# HealthMonitor.net
KiCad netlist of a schematic drawn in EAGLE
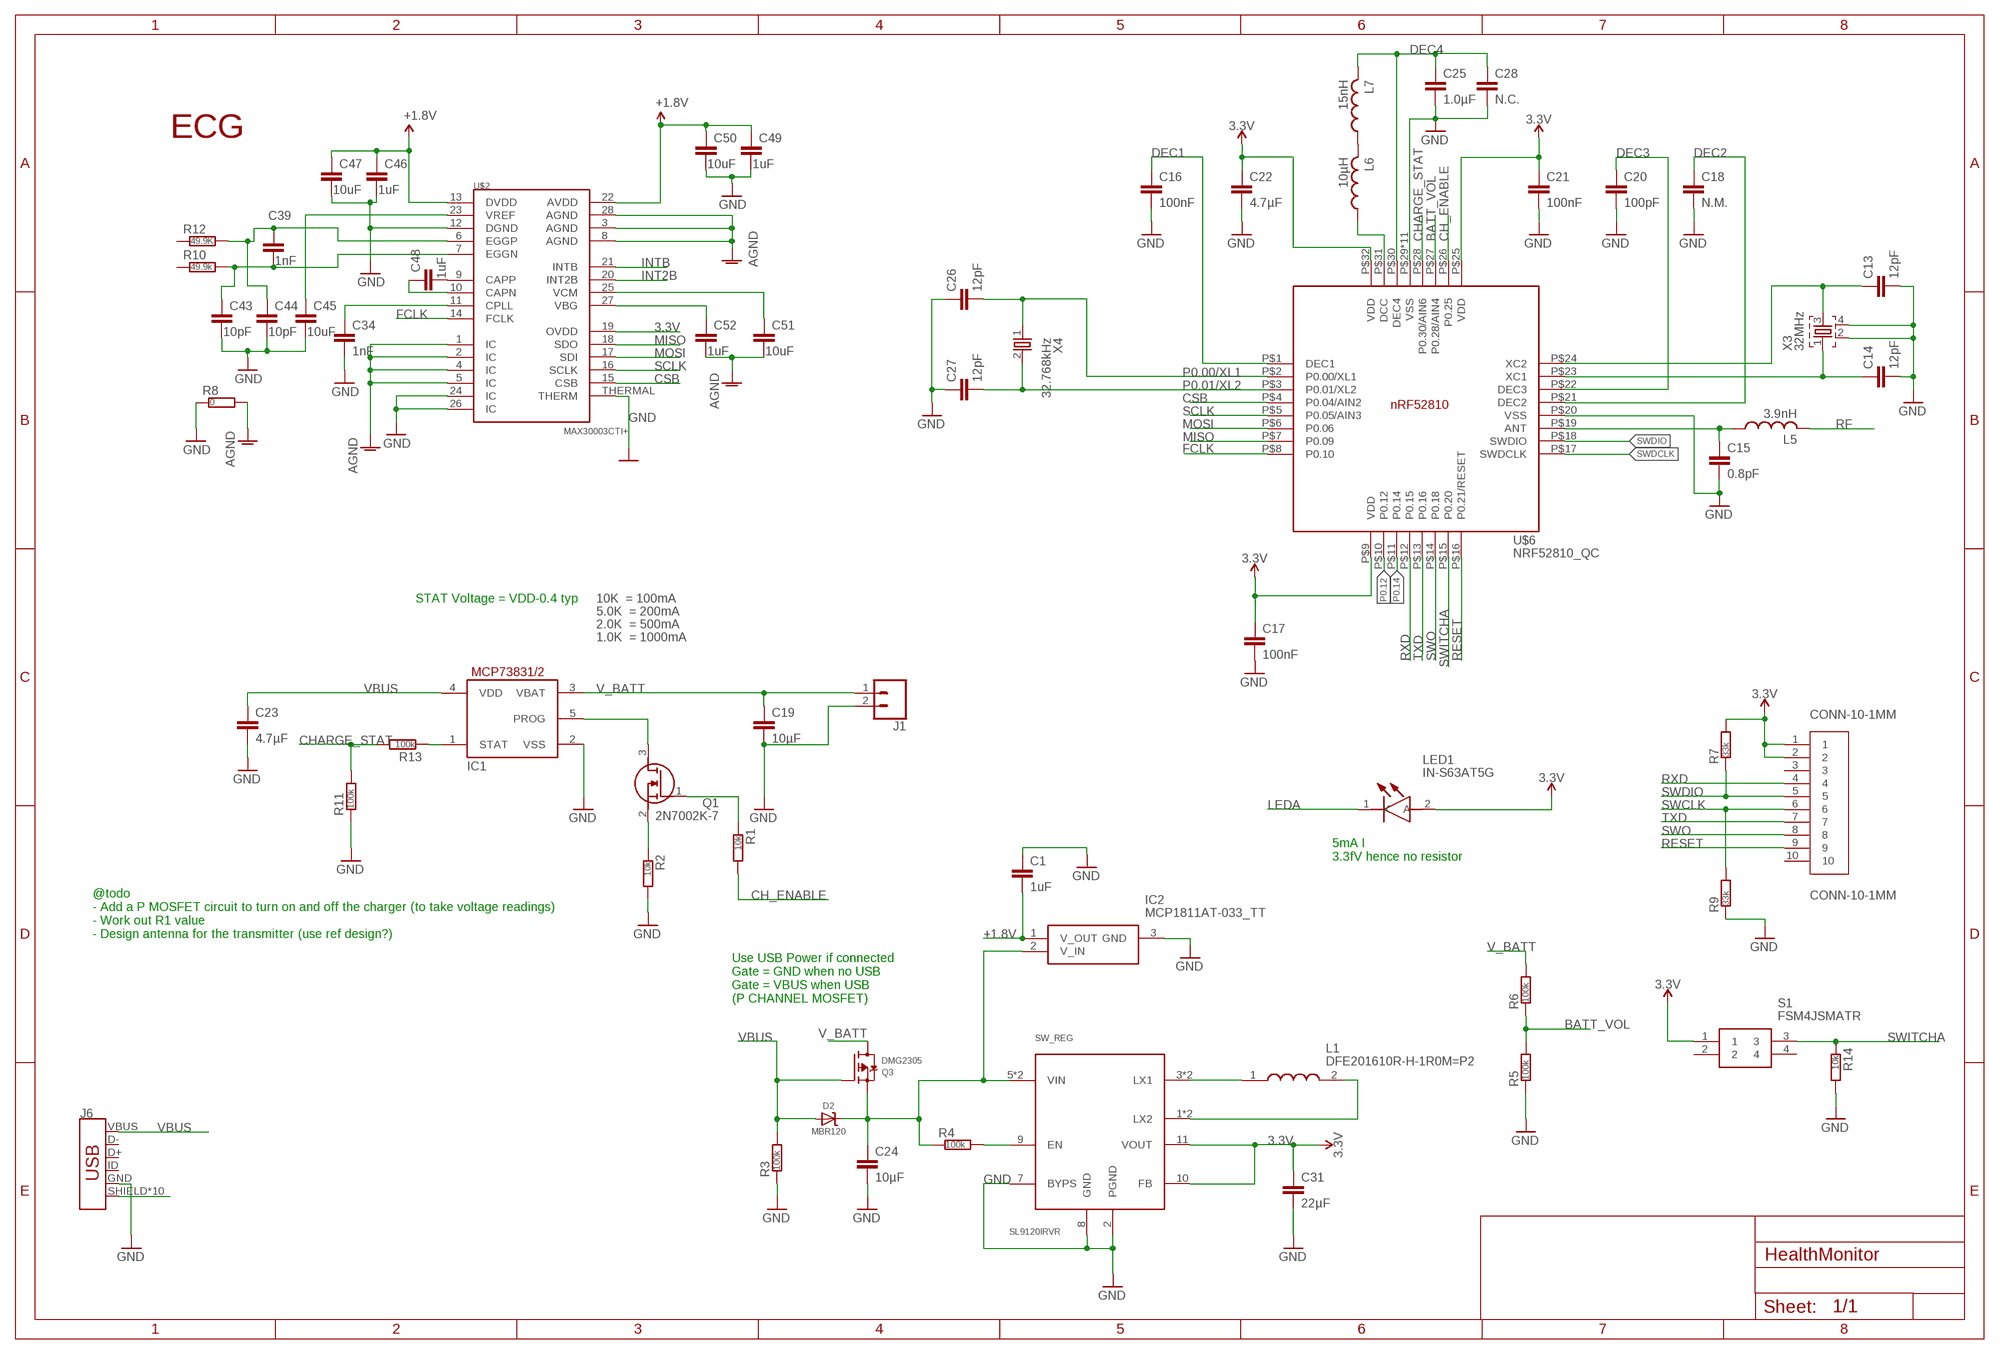
[diagram p0: schematic, sheet 1]

(export (version "E")
  (design (tool "Eeschema 10.0.6"))
  (components
    (comp (ref "C1")
      (value "1uF")
      (footprint "eagle-import:RESC0402_N")
      (libsource (lib "eagle-import") (part "CAPACITOR_0402_N"))
    )
    (comp (ref "C13")
      (value "12pF")
      (footprint "eagle-import:RESC0402_N")
      (libsource (lib "eagle-import") (part "CAPACITOR_0402_N"))
    )
    (comp (ref "C14")
      (value "12pF")
      (footprint "eagle-import:RESC0402_N")
      (libsource (lib "eagle-import") (part "CAPACITOR_0402_N"))
    )
    (comp (ref "C15")
      (value "0.8pF")
      (footprint "eagle-import:RESC0402_N")
      (libsource (lib "eagle-import") (part "CAPACITOR_0402_N"))
    )
    (comp (ref "C16")
      (value "100nF")
      (footprint "eagle-import:RESC0402_N")
      (libsource (lib "eagle-import") (part "CAPACITOR_0402_N"))
    )
    (comp (ref "C17")
      (value "100nF")
      (footprint "eagle-import:RESC0402_N")
      (libsource (lib "eagle-import") (part "CAPACITOR_0402_N"))
    )
    (comp (ref "C18")
      (value "N.M.")
      (footprint "eagle-import:RESC0402_N")
      (libsource (lib "eagle-import") (part "CAPACITOR_0402_N"))
    )
    (comp (ref "C19")
      (value "10µF")
      (footprint "eagle-import:RESC0603_N")
      (libsource (lib "eagle-import") (part "CAPACITOR_0603_N"))
    )
    (comp (ref "C20")
      (value "100pF")
      (footprint "eagle-import:RESC0402_N")
      (libsource (lib "eagle-import") (part "CAPACITOR_0402_N"))
    )
    (comp (ref "C21")
      (value "100nF")
      (footprint "eagle-import:RESC0402_N")
      (libsource (lib "eagle-import") (part "CAPACITOR_0402_N"))
    )
    (comp (ref "C22")
      (value "4.7µF")
      (footprint "eagle-import:RESC0603_N")
      (libsource (lib "eagle-import") (part "CAPACITOR_0603_N"))
    )
    (comp (ref "C23")
      (value "4.7µF")
      (footprint "eagle-import:RESC0603_N")
      (libsource (lib "eagle-import") (part "CAPACITOR_0603_N"))
    )
    (comp (ref "C24")
      (value "10µF")
      (footprint "eagle-import:RESC0603_N")
      (libsource (lib "eagle-import") (part "CAPACITOR_0603_N"))
    )
    (comp (ref "C25")
      (value "1.0µF")
      (footprint "eagle-import:RESC0603_N")
      (libsource (lib "eagle-import") (part "CAPACITOR_0603_N"))
    )
    (comp (ref "C26")
      (value "12pF")
      (footprint "eagle-import:RESC0402_N")
      (libsource (lib "eagle-import") (part "CAPACITOR_0402_N"))
    )
    (comp (ref "C27")
      (value "12pF")
      (footprint "eagle-import:RESC0402_N")
      (libsource (lib "eagle-import") (part "CAPACITOR_0402_N"))
    )
    (comp (ref "C28")
      (value "N.C.")
      (footprint "eagle-import:RESC0402_N")
      (libsource (lib "eagle-import") (part "CAPACITOR_0402_N"))
    )
    (comp (ref "C31")
      (value "22µF")
      (footprint "eagle-import:RESC0603_N")
      (libsource (lib "eagle-import") (part "CAPACITOR_0603_N"))
    )
    (comp (ref "C34")
      (value "1nF")
      (footprint "eagle-import:C0805")
      (libsource (lib "eagle-import") (part "C-EUC0805"))
    )
    (comp (ref "C39")
      (value "1nF")
      (footprint "eagle-import:RESC0603_N")
      (libsource (lib "eagle-import") (part "CAPACITOR_0603_N"))
    )
    (comp (ref "C43")
      (value "10pF")
      (footprint "eagle-import:RESC0603_N")
      (libsource (lib "eagle-import") (part "CAPACITOR_0603_N"))
    )
    (comp (ref "C44")
      (value "10pF")
      (footprint "eagle-import:RESC0603_N")
      (libsource (lib "eagle-import") (part "CAPACITOR_0603_N"))
    )
    (comp (ref "C45")
      (value "10uF")
      (footprint "eagle-import:RESC0603_N")
      (libsource (lib "eagle-import") (part "CAPACITOR_0603_N"))
    )
    (comp (ref "C46")
      (value "1uF")
      (footprint "eagle-import:RESC0603_N")
      (libsource (lib "eagle-import") (part "CAPACITOR_0603_N"))
    )
    (comp (ref "C47")
      (value "10uF")
      (footprint "eagle-import:RESC0603_N")
      (libsource (lib "eagle-import") (part "CAPACITOR_0603_N"))
    )
    (comp (ref "C48")
      (value "1uF")
      (footprint "eagle-import:RESC0603_N")
      (libsource (lib "eagle-import") (part "CAPACITOR_0603_N"))
    )
    (comp (ref "C49")
      (value "1uF")
      (footprint "eagle-import:RESC0603_N")
      (libsource (lib "eagle-import") (part "CAPACITOR_0603_N"))
    )
    (comp (ref "C50")
      (value "10uF")
      (footprint "eagle-import:RESC0603_N")
      (libsource (lib "eagle-import") (part "CAPACITOR_0603_N"))
    )
    (comp (ref "C51")
      (value "10uF")
      (footprint "eagle-import:RESC0603_N")
      (libsource (lib "eagle-import") (part "CAPACITOR_0603_N"))
    )
    (comp (ref "C52")
      (value "1uF")
      (footprint "eagle-import:RESC0603_N")
      (libsource (lib "eagle-import") (part "CAPACITOR_0603_N"))
    )
    (comp (ref "D2")
      (value "MBR120")
      (footprint "eagle-import:SOD-123")
      (libsource (lib "eagle-import") (part "DIODE-SCHOTTKYSOD-123"))
    )
    (comp (ref "IC1")
      (value "MCP73831/OT")
      (footprint "eagle-import:SOT23-5L")
      (libsource (lib "eagle-import") (part "MCP73831/OT"))
    )
    (comp (ref "IC2")
      (value "MCP1811AT-033_TT")
      (footprint "eagle-import:SOT95P237X112-3N")
      (fields
        (field (name "MANUFACTURER_PART_NUMBER") "MCP1811AT-033/TT")
        (field (name "MOUSER_PART_NUMBER") "579-MCP1811AT-033/TT")
      )
      (libsource (lib "eagle-import") (part "MCP1811AT-033_TT"))
    )
    (comp (ref "J1")
      (value "CONN_02")
      (footprint "eagle-import:1X02")
      (libsource (lib "eagle-import") (part "CONN_02"))
    )
    (comp (ref "J6")
      (value "USB_MICRO-B_HALF_PTH_MILL")
      (footprint "eagle-import:USB-MICROB-PTH-MILL")
      (libsource (lib "eagle-import") (part "USB_MICRO-B_HALF_PTH_MILL"))
    )
    (comp (ref "L1")
      (value "DFE201610R-H-1R0M=P2")
      (footprint "eagle-import:INDC2016X100N")
      (fields (field (name "MOUSER_PART_NUMBER") "81-DFE201610RH1R0MP2"))
      (libsource (lib "eagle-import") (part "DFE201610R-H-1R0M=P2"))
    )
    (comp (ref "L5")
      (value "3.9nH")
      (footprint "eagle-import:RESC0402_N")
      (libsource (lib "eagle-import") (part "INDUCTOR_0402_N"))
    )
    (comp (ref "L6")
      (value "10µH")
      (footprint "eagle-import:RESC0603_N")
      (libsource (lib "eagle-import") (part "INDUCTOR_0603_N"))
    )
    (comp (ref "L7")
      (value "15nH")
      (footprint "eagle-import:RESC0402_N")
      (libsource (lib "eagle-import") (part "INDUCTOR_0402_N"))
    )
    (comp (ref "LED1")
      (value "IN-S63AT5G")
      (footprint "eagle-import:LEDM168X39N")
      (fields (field (name "MOUSER_PART_NUMBER") "743-IN-S63AT5G"))
      (libsource (lib "eagle-import") (part "IN-S63AT5G"))
    )
    (comp (ref "Q1")
      (value "2N7002K-7")
      (footprint "eagle-import:SOT96P240X100-3N")
      (fields (field (name "MOUSER_PART_NUMBER") "621-2N7002K-7") (field (name "RS_PART_NUMBER") "7703383"))
      (libsource (lib "eagle-import") (part "2N7002K-7"))
    )
    (comp (ref "Q3")
      (value "DMG2305")
      (footprint "eagle-import:SOT23-R")
      (libsource (lib "eagle-import") (part "MOSFET-P"))
    )
    (comp (ref "R1")
      (value "10k")
      (footprint "eagle-import:RESC0402_N")
      (libsource (lib "eagle-import") (part "RESISTOR_0402_N"))
    )
    (comp (ref "R2")
      (value "10k")
      (footprint "eagle-import:RESC0402_N")
      (libsource (lib "eagle-import") (part "RESISTOR_0402_N"))
    )
    (comp (ref "R3")
      (value "100k")
      (footprint "eagle-import:RESC0402_N")
      (libsource (lib "eagle-import") (part "RESISTOR_0402_N"))
    )
    (comp (ref "R4")
      (value "100k")
      (footprint "eagle-import:RESC0402_N")
      (libsource (lib "eagle-import") (part "RESISTOR_0402_N"))
    )
    (comp (ref "R5")
      (value "100k")
      (footprint "eagle-import:RESC0402_N")
      (libsource (lib "eagle-import") (part "RESISTOR_0402_N"))
    )
    (comp (ref "R6")
      (value "100k")
      (footprint "eagle-import:RESC0402_N")
      (libsource (lib "eagle-import") (part "RESISTOR_0402_N"))
    )
    (comp (ref "R7")
      (value "33k")
      (footprint "eagle-import:RESC0402_N")
      (libsource (lib "eagle-import") (part "RESISTOR_0402_N"))
    )
    (comp (ref "R8")
      (value "0")
      (footprint "eagle-import:RESC0402_N")
      (libsource (lib "eagle-import") (part "RESISTOR_0402_N"))
    )
    (comp (ref "R9")
      (value "33k")
      (footprint "eagle-import:RESC0402_N")
      (libsource (lib "eagle-import") (part "RESISTOR_0402_N"))
    )
    (comp (ref "R10")
      (value "49.9k")
      (footprint "eagle-import:RESC0402_N")
      (libsource (lib "eagle-import") (part "RESISTOR_0402_N"))
    )
    (comp (ref "R11")
      (value "100k")
      (footprint "eagle-import:RESC0402_N")
      (libsource (lib "eagle-import") (part "RESISTOR_0402_N"))
    )
    (comp (ref "R12")
      (value "49.9K")
      (footprint "eagle-import:RESC0402_N")
      (libsource (lib "eagle-import") (part "RESISTOR_0402_N"))
    )
    (comp (ref "R13")
      (value "100k")
      (footprint "eagle-import:RESC0402_N")
      (libsource (lib "eagle-import") (part "RESISTOR_0402_N"))
    )
    (comp (ref "R14")
      (value "10k")
      (footprint "eagle-import:RESC0402_N")
      (libsource (lib "eagle-import") (part "RESISTOR_0402_N"))
    )
    (comp (ref "S1")
      (value "FSM4JSMATR")
      (footprint "eagle-import:FSM4JSMATR")
      (fields (field (name "MOUSER_PART_NUMBER") "506-FSM4JSMATR") (field (name "RS_PART_NUMBER") "7182455P"))
      (libsource (lib "eagle-import") (part "FSM4JSMATR"))
    )
    (comp (ref "SW_REG")
      (value "SL9120IRVR")
      (footprint "eagle-import:TQFN-12")
      (libsource (lib "eagle-import") (part "SL9120IRVR"))
    )
    (comp (ref "U$1")
      (value "CONN-10-1MM")
      (footprint "eagle-import:CONN-10-1MM")
      (libsource (lib "eagle-import") (part "CONN-10-1MM"))
    )
    (comp (ref "U$2")
      (value "MAX30003CTI+")
      (footprint "eagle-import:QFN-28")
      (libsource (lib "eagle-import") (part "MAX30003"))
    )
    (comp (ref "U$6")
      (value "NRF52810_QC")
      (footprint "eagle-import:QFN50P500X500X90-32_N")
      (libsource (lib "eagle-import") (part "NRF52810_QC"))
    )
    (comp (ref "X3")
      (value "32MHz")
      (footprint "eagle-import:BT-XTAL_2016_N")
      (libsource (lib "eagle-import") (part "XTAL_32MHZ"))
    )
    (comp (ref "X4")
      (value "32.768kHz")
      (footprint "eagle-import:XTAL_3215_N")
      (libsource (lib "eagle-import") (part "XTAL_32KHZ"))
    )
  )
  (nets
    (net (code "1") (name "+1.8V") (class "Default")
      (node (ref "C1") (pin "2") (pinfunction "2_2") (pintype "passive"))
      (node (ref "C46") (pin "1") (pinfunction "1_1") (pintype "passive"))
      (node (ref "C47") (pin "1") (pinfunction "1_1") (pintype "passive"))
      (node (ref "C49") (pin "1") (pinfunction "1_1") (pintype "passive"))
      (node (ref "C50") (pin "1") (pinfunction "1_1") (pintype "passive"))
      (node (ref "IC2") (pin "1") (pinfunction "V_OUT_1") (pintype "bidirectional"))
      (node (ref "U$2") (pin "13") (pinfunction "DVDD_13") (pintype "bidirectional"))
      (node (ref "U$2") (pin "22") (pinfunction "AVDD_22") (pintype "bidirectional"))
    )
    (net (code "2") (name "/BATT_VOL") (class "Default")
      (node (ref "R5") (pin "2") (pinfunction "2_2") (pintype "passive"))
      (node (ref "R6") (pin "1") (pinfunction "1_1") (pintype "passive"))
      (node (ref "U$6") (pin "P$27") (pinfunction "P0.28/AIN4_P$27") (pintype "bidirectional"))
    )
    (net (code "3") (name "/CHARGE_STAT") (class "Default")
      (node (ref "R11") (pin "2") (pinfunction "2_2") (pintype "passive"))
      (node (ref "R13") (pin "2") (pinfunction "2_2") (pintype "passive"))
      (node (ref "U$6") (pin "P$28") (pinfunction "P0.30/AIN6_P$28") (pintype "bidirectional"))
    )
    (net (code "4") (name "/CH_ENABLE") (class "Default")
      (node (ref "R1") (pin "2") (pinfunction "2_2") (pintype "passive"))
      (node (ref "U$6") (pin "P$26") (pinfunction "P0.25_P$26") (pintype "bidirectional"))
    )
    (net (code "5") (name "/CSB") (class "Default")
      (node (ref "U$2") (pin "15") (pinfunction "CSB_15") (pintype "bidirectional"))
      (node (ref "U$6") (pin "P$4") (pinfunction "P0.04/AIN2_P$4") (pintype "bidirectional"))
    )
    (net (code "6") (name "/DEC1") (class "Default")
      (node (ref "C16") (pin "1") (pinfunction "1_1") (pintype "passive"))
      (node (ref "U$6") (pin "P$1") (pinfunction "DEC1_P$1") (pintype "bidirectional"))
    )
    (net (code "7") (name "/DEC2") (class "Default")
      (node (ref "C18") (pin "1") (pinfunction "1_1") (pintype "passive"))
      (node (ref "U$6") (pin "P$21") (pinfunction "DEC2_P$21") (pintype "bidirectional"))
    )
    (net (code "8") (name "/DEC3") (class "Default")
      (node (ref "C20") (pin "1") (pinfunction "1_1") (pintype "passive"))
      (node (ref "U$6") (pin "P$22") (pinfunction "DEC3_P$22") (pintype "bidirectional"))
    )
    (net (code "9") (name "/DEC4") (class "Default")
      (node (ref "C25") (pin "1") (pinfunction "1_1") (pintype "passive"))
      (node (ref "C28") (pin "1") (pinfunction "1_1") (pintype "passive"))
      (node (ref "L7") (pin "2") (pinfunction "2_2") (pintype "passive"))
      (node (ref "U$6") (pin "P$30") (pinfunction "DEC4_P$30") (pintype "bidirectional"))
    )
    (net (code "10") (name "/FCLK") (class "Default")
      (node (ref "U$2") (pin "14") (pinfunction "FCLK_14") (pintype "bidirectional"))
      (node (ref "U$6") (pin "P$8") (pinfunction "P0.10_P$8") (pintype "bidirectional"))
    )
    (net (code "11") (name "/INT2B") (class "Default")
      (node (ref "U$2") (pin "20") (pinfunction "INT2B_20") (pintype "bidirectional"))
    )
    (net (code "12") (name "/INTB") (class "Default")
      (node (ref "U$2") (pin "21") (pinfunction "INTB_21") (pintype "bidirectional"))
    )
    (net (code "13") (name "/LEDA") (class "Default")
      (node (ref "LED1") (pin "1") (pinfunction "K_1") (pintype "bidirectional"))
    )
    (net (code "14") (name "/MISO") (class "Default")
      (node (ref "U$2") (pin "18") (pinfunction "SDO_18") (pintype "bidirectional"))
      (node (ref "U$6") (pin "P$7") (pinfunction "P0.09_P$7") (pintype "bidirectional"))
    )
    (net (code "15") (name "/MOSI") (class "Default")
      (node (ref "U$2") (pin "17") (pinfunction "SDI_17") (pintype "bidirectional"))
      (node (ref "U$6") (pin "P$6") (pinfunction "P0.06_P$6") (pintype "bidirectional"))
    )
    (net (code "16") (name "/P0.00{slash}XL1") (class "Default")
      (node (ref "C26") (pin "2") (pinfunction "2_2") (pintype "passive"))
      (node (ref "U$6") (pin "P$2") (pinfunction "P0.00/XL1_P$2") (pintype "bidirectional"))
      (node (ref "X4") (pin "1") (pinfunction "1_1") (pintype "passive"))
    )
    (net (code "17") (name "/P0.01{slash}XL2") (class "Default")
      (node (ref "C27") (pin "2") (pinfunction "2_2") (pintype "passive"))
      (node (ref "U$6") (pin "P$3") (pinfunction "P0.01/XL2_P$3") (pintype "bidirectional"))
      (node (ref "X4") (pin "2") (pinfunction "2_2") (pintype "passive"))
    )
    (net (code "18") (name "/RESET") (class "Default")
      (node (ref "U$1") (pin "9") (pinfunction "9_9") (pintype "bidirectional"))
      (node (ref "U$6") (pin "P$16") (pinfunction "P0.21/RESET_P$16") (pintype "bidirectional"))
    )
    (net (code "19") (name "/RF") (class "Default")
      (node (ref "L5") (pin "2") (pinfunction "2_2") (pintype "passive"))
    )
    (net (code "20") (name "/RXD") (class "Default")
      (node (ref "U$1") (pin "4") (pinfunction "4_4") (pintype "bidirectional"))
      (node (ref "U$6") (pin "P$12") (pinfunction "P0.15_P$12") (pintype "bidirectional"))
    )
    (net (code "21") (name "/SCLK") (class "Default")
      (node (ref "U$2") (pin "16") (pinfunction "SCLK_16") (pintype "bidirectional"))
      (node (ref "U$6") (pin "P$5") (pinfunction "P0.05/AIN3_P$5") (pintype "bidirectional"))
    )
    (net (code "22") (name "/SWCLK") (class "Default")
      (node (ref "R9") (pin "2") (pinfunction "2_2") (pintype "passive"))
      (node (ref "U$1") (pin "6") (pinfunction "6_6") (pintype "bidirectional"))
    )
    (net (code "23") (name "/SWITCHA") (class "Default")
      (node (ref "R14") (pin "1") (pinfunction "1_1") (pintype "passive"))
      (node (ref "S1") (pin "3") (pinfunction "3_3") (pintype "bidirectional"))
      (node (ref "U$6") (pin "P$15") (pinfunction "P0.20_P$15") (pintype "bidirectional"))
    )
    (net (code "24") (name "/SWO") (class "Default")
      (node (ref "U$1") (pin "8") (pinfunction "8_8") (pintype "bidirectional"))
      (node (ref "U$6") (pin "P$14") (pinfunction "P0.18_P$14") (pintype "bidirectional"))
    )
    (net (code "25") (name "/TXD") (class "Default")
      (node (ref "U$1") (pin "7") (pinfunction "7_7") (pintype "bidirectional"))
      (node (ref "U$6") (pin "P$13") (pinfunction "P0.16_P$13") (pintype "bidirectional"))
    )
    (net (code "26") (name "/VBUS") (class "Default")
      (node (ref "C23") (pin "1") (pinfunction "1_1") (pintype "passive"))
      (node (ref "D2") (pin "A") (pinfunction "A_A") (pintype "passive"))
      (node (ref "IC1") (pin "4") (pinfunction "VDD_4") (pintype "power_in"))
      (node (ref "J6") (pin "VBUS") (pinfunction "VBUS_VBUS") (pintype "power_in"))
      (node (ref "Q3") (pin "1") (pinfunction "G_1") (pintype "passive"))
      (node (ref "R3") (pin "2") (pinfunction "2_2") (pintype "passive"))
    )
    (net (code "27") (name "/V_BATT") (class "Default")
      (node (ref "C19") (pin "1") (pinfunction "1_1") (pintype "passive"))
      (node (ref "IC1") (pin "3") (pinfunction "VBAT_3") (pintype "bidirectional"))
      (node (ref "J1") (pin "1") (pinfunction "1_1") (pintype "passive"))
      (node (ref "Q3") (pin "3") (pinfunction "D_3") (pintype "passive"))
      (node (ref "R6") (pin "2") (pinfunction "2_2") (pintype "passive"))
    )
    (net (code "28") (name "3.3V") (class "Default")
      (node (ref "C17") (pin "1") (pinfunction "1_1") (pintype "passive"))
      (node (ref "C21") (pin "1") (pinfunction "1_1") (pintype "passive"))
      (node (ref "C22") (pin "1") (pinfunction "1_1") (pintype "passive"))
      (node (ref "C31") (pin "1") (pinfunction "1_1") (pintype "passive"))
      (node (ref "LED1") (pin "2") (pinfunction "A_2") (pintype "bidirectional"))
      (node (ref "R7") (pin "2") (pinfunction "2_2") (pintype "passive"))
      (node (ref "S1") (pin "1") (pinfunction "1_1") (pintype "bidirectional"))
      (node (ref "SW_REG") (pin "10") (pinfunction "FB_10") (pintype "bidirectional"))
      (node (ref "SW_REG") (pin "11") (pinfunction "VOUT_11") (pintype "bidirectional"))
      (node (ref "U$1") (pin "1") (pinfunction "1_1") (pintype "bidirectional"))
      (node (ref "U$1") (pin "2") (pinfunction "2_2") (pintype "bidirectional"))
      (node (ref "U$2") (pin "19") (pinfunction "OVDD_19") (pintype "bidirectional"))
      (node (ref "U$6") (pin "P$25") (pinfunction "VDD_P$25") (pintype "bidirectional"))
      (node (ref "U$6") (pin "P$32") (pinfunction "VDD_P$32") (pintype "bidirectional"))
      (node (ref "U$6") (pin "P$9") (pinfunction "VDD_P$9") (pintype "bidirectional"))
    )
    (net (code "29") (name "AGND") (class "Default")
      (node (ref "C51") (pin "2") (pinfunction "2_2") (pintype "passive"))
      (node (ref "C52") (pin "2") (pinfunction "2_2") (pintype "passive"))
      (node (ref "R8") (pin "2") (pinfunction "2_2") (pintype "passive"))
      (node (ref "U$2") (pin "1") (pinfunction "IC_1") (pintype "bidirectional"))
      (node (ref "U$2") (pin "2") (pinfunction "IC_2") (pintype "bidirectional"))
      (node (ref "U$2") (pin "28") (pinfunction "AGND_28") (pintype "bidirectional"))
      (node (ref "U$2") (pin "3") (pinfunction "AGND_3") (pintype "bidirectional"))
      (node (ref "U$2") (pin "4") (pinfunction "IC_4") (pintype "bidirectional"))
      (node (ref "U$2") (pin "5") (pinfunction "IC_5") (pintype "bidirectional"))
      (node (ref "U$2") (pin "8") (pinfunction "AGND_8") (pintype "bidirectional"))
    )
    (net (code "30") (name "GND") (class "Default")
      (node (ref "C1") (pin "1") (pinfunction "1_1") (pintype "passive"))
      (node (ref "C13") (pin "2") (pinfunction "2_2") (pintype "passive"))
      (node (ref "C14") (pin "2") (pinfunction "2_2") (pintype "passive"))
      (node (ref "C15") (pin "2") (pinfunction "2_2") (pintype "passive"))
      (node (ref "C16") (pin "2") (pinfunction "2_2") (pintype "passive"))
      (node (ref "C17") (pin "2") (pinfunction "2_2") (pintype "passive"))
      (node (ref "C18") (pin "2") (pinfunction "2_2") (pintype "passive"))
      (node (ref "C19") (pin "2") (pinfunction "2_2") (pintype "passive"))
      (node (ref "C20") (pin "2") (pinfunction "2_2") (pintype "passive"))
      (node (ref "C21") (pin "2") (pinfunction "2_2") (pintype "passive"))
      (node (ref "C22") (pin "2") (pinfunction "2_2") (pintype "passive"))
      (node (ref "C23") (pin "2") (pinfunction "2_2") (pintype "passive"))
      (node (ref "C24") (pin "2") (pinfunction "2_2") (pintype "passive"))
      (node (ref "C25") (pin "2") (pinfunction "2_2") (pintype "passive"))
      (node (ref "C26") (pin "1") (pinfunction "1_1") (pintype "passive"))
      (node (ref "C27") (pin "1") (pinfunction "1_1") (pintype "passive"))
      (node (ref "C28") (pin "2") (pinfunction "2_2") (pintype "passive"))
      (node (ref "C31") (pin "2") (pinfunction "2_2") (pintype "passive"))
      (node (ref "C34") (pin "2") (pinfunction "2_2") (pintype "passive"))
      (node (ref "C43") (pin "2") (pinfunction "2_2") (pintype "passive"))
      (node (ref "C44") (pin "2") (pinfunction "2_2") (pintype "passive"))
      (node (ref "C45") (pin "2") (pinfunction "2_2") (pintype "passive"))
      (node (ref "C46") (pin "2") (pinfunction "2_2") (pintype "passive"))
      (node (ref "C47") (pin "2") (pinfunction "2_2") (pintype "passive"))
      (node (ref "C49") (pin "2") (pinfunction "2_2") (pintype "passive"))
      (node (ref "C50") (pin "2") (pinfunction "2_2") (pintype "passive"))
      (node (ref "IC1") (pin "2") (pinfunction "VSS_2") (pintype "power_in"))
      (node (ref "IC2") (pin "3") (pinfunction "GND_3") (pintype "bidirectional"))
      (node (ref "J1") (pin "2") (pinfunction "2_2") (pintype "passive"))
      (node (ref "J6") (pin "GND") (pinfunction "GND_GND") (pintype "power_in"))
      (node (ref "R11") (pin "1") (pinfunction "1_1") (pintype "passive"))
      (node (ref "R14") (pin "2") (pinfunction "2_2") (pintype "passive"))
      (node (ref "R2") (pin "2") (pinfunction "2_2") (pintype "passive"))
      (node (ref "R3") (pin "1") (pinfunction "1_1") (pintype "passive"))
      (node (ref "R5") (pin "1") (pinfunction "1_1") (pintype "passive"))
      (node (ref "R8") (pin "1") (pinfunction "1_1") (pintype "passive"))
      (node (ref "R9") (pin "1") (pinfunction "1_1") (pintype "passive"))
      (node (ref "SW_REG") (pin "2") (pinfunction "PGND_2") (pintype "bidirectional"))
      (node (ref "SW_REG") (pin "7") (pinfunction "BYPS_7") (pintype "bidirectional"))
      (node (ref "SW_REG") (pin "8") (pinfunction "GND_8") (pintype "bidirectional"))
      (node (ref "U$2") (pin "12") (pinfunction "DGND_12") (pintype "bidirectional"))
      (node (ref "U$2") (pin "24") (pinfunction "IC_24") (pintype "bidirectional"))
      (node (ref "U$2") (pin "26") (pinfunction "IC_26") (pintype "bidirectional"))
      (node (ref "U$2") (pin "THERMAL") (pinfunction "THERM_THERMAL") (pintype "bidirectional"))
      (node (ref "U$6") (pin "P$20") (pinfunction "VSS_P$20") (pintype "bidirectional"))
      (node (ref "U$6") (pin "P$29") (pinfunction "VSS_P$29") (pintype "bidirectional"))
      (node (ref "U$6") (pin "P$33") (pinfunction "VSS_P$33") (pintype "bidirectional"))
      (node (ref "U$6") (pin "P$34") (pinfunction "VSS_P$34") (pintype "bidirectional"))
      (node (ref "U$6") (pin "P$35") (pinfunction "VSS_P$35") (pintype "bidirectional"))
      (node (ref "U$6") (pin "P$36") (pinfunction "VSS_P$36") (pintype "bidirectional"))
      (node (ref "U$6") (pin "P$37") (pinfunction "VSS_P$37") (pintype "bidirectional"))
      (node (ref "U$6") (pin "P$38") (pinfunction "VSS_P$38") (pintype "bidirectional"))
      (node (ref "U$6") (pin "P$39") (pinfunction "VSS_P$39") (pintype "bidirectional"))
      (node (ref "U$6") (pin "P$40") (pinfunction "VSS_P$40") (pintype "bidirectional"))
      (node (ref "U$6") (pin "P$41") (pinfunction "VSS_P$41") (pintype "bidirectional"))
      (node (ref "U$6") (pin "P$42") (pinfunction "VSS_P$42") (pintype "bidirectional"))
      (node (ref "X3") (pin "2") (pinfunction "2_2") (pintype "passive"))
      (node (ref "X3") (pin "4") (pinfunction "4_4") (pintype "passive"))
    )
    (net (code "31") (name "Net-(IC1-PROG)") (class "Default")
      (node (ref "IC1") (pin "5") (pinfunction "PROG_5") (pintype "input"))
      (node (ref "Q1") (pin "3") (pinfunction "D_3") (pintype "bidirectional"))
    )
    (net (code "32") (name "Net-(IC1-STAT)") (class "Default")
      (node (ref "IC1") (pin "1") (pinfunction "STAT_1") (pintype "output"))
      (node (ref "R13") (pin "1") (pinfunction "1_1") (pintype "passive"))
    )
    (net (code "33") (name "Net-(IC2-V_IN)") (class "Default")
      (node (ref "C24") (pin "1") (pinfunction "1_1") (pintype "passive"))
      (node (ref "D2") (pin "C") (pinfunction "C_C") (pintype "passive"))
      (node (ref "IC2") (pin "2") (pinfunction "V_IN_2") (pintype "bidirectional"))
      (node (ref "Q3") (pin "2") (pinfunction "S_2") (pintype "passive"))
      (node (ref "R4") (pin "1") (pinfunction "1_1") (pintype "passive"))
      (node (ref "SW_REG") (pin "5") (pinfunction "VIN_5") (pintype "bidirectional"))
      (node (ref "SW_REG") (pin "6") (pinfunction "VIN_6") (pintype "bidirectional"))
    )
    (net (code "34") (name "Net-(J6-PadSHIELD)") (class "Default")
      (node (ref "J6") (pin "SHIELD") (pinfunction "SHIELD_SHIELD") (pintype "bidirectional"))
      (node (ref "J6") (pin "SHIELD10") (pinfunction "SHIELD_SHIELD10") (pintype "bidirectional"))
      (node (ref "J6") (pin "SHIELD2") (pinfunction "SHIELD_SHIELD2") (pintype "bidirectional"))
      (node (ref "J6") (pin "SHIELD3") (pinfunction "SHIELD_SHIELD3") (pintype "bidirectional"))
      (node (ref "J6") (pin "SHIELD4") (pinfunction "SHIELD_SHIELD4") (pintype "bidirectional"))
      (node (ref "J6") (pin "SHIELD5") (pinfunction "SHIELD_SHIELD5") (pintype "bidirectional"))
      (node (ref "J6") (pin "SHIELD6") (pinfunction "SHIELD_SHIELD6") (pintype "bidirectional"))
      (node (ref "J6") (pin "SHIELD7") (pinfunction "SHIELD_SHIELD7") (pintype "bidirectional"))
      (node (ref "J6") (pin "SHIELD8") (pinfunction "SHIELD_SHIELD8") (pintype "bidirectional"))
      (node (ref "J6") (pin "SHIELD9") (pinfunction "SHIELD_SHIELD9") (pintype "bidirectional"))
    )
    (net (code "35") (name "Net-(L1-Pad1)") (class "Default")
      (node (ref "L1") (pin "1") (pinfunction "1_1") (pintype "bidirectional"))
      (node (ref "SW_REG") (pin "3") (pinfunction "LX1_3") (pintype "bidirectional"))
      (node (ref "SW_REG") (pin "4") (pinfunction "LX1_4") (pintype "bidirectional"))
    )
    (net (code "36") (name "Net-(L1-Pad2)") (class "Default")
      (node (ref "L1") (pin "2") (pinfunction "2_2") (pintype "bidirectional"))
      (node (ref "SW_REG") (pin "1") (pinfunction "LX2_1") (pintype "bidirectional"))
      (node (ref "SW_REG") (pin "12") (pinfunction "LX2_12") (pintype "bidirectional"))
    )
    (net (code "37") (name "Net-(L6-Pad2)") (class "Default")
      (node (ref "L6") (pin "2") (pinfunction "2_2") (pintype "passive"))
      (node (ref "L7") (pin "1") (pinfunction "1_1") (pintype "passive"))
    )
    (net (code "38") (name "Net-(Q1-G)") (class "Default")
      (node (ref "Q1") (pin "1") (pinfunction "G_1") (pintype "bidirectional"))
      (node (ref "R1") (pin "1") (pinfunction "1_1") (pintype "passive"))
    )
    (net (code "39") (name "Net-(Q1-S)") (class "Default")
      (node (ref "Q1") (pin "2") (pinfunction "S_2") (pintype "bidirectional"))
      (node (ref "R2") (pin "1") (pinfunction "1_1") (pintype "passive"))
    )
    (net (code "40") (name "Net-(SW_REG-EN)") (class "Default")
      (node (ref "R4") (pin "2") (pinfunction "2_2") (pintype "passive"))
      (node (ref "SW_REG") (pin "9") (pinfunction "EN_9") (pintype "bidirectional"))
    )
    (net (code "41") (name "Net-(U$2-CAPN)") (class "Default")
      (node (ref "C48") (pin "1") (pinfunction "1_1") (pintype "passive"))
      (node (ref "U$2") (pin "10") (pinfunction "CAPN_10") (pintype "bidirectional"))
    )
    (net (code "42") (name "Net-(U$2-CAPP)") (class "Default")
      (node (ref "C48") (pin "2") (pinfunction "2_2") (pintype "passive"))
      (node (ref "U$2") (pin "9") (pinfunction "CAPP_9") (pintype "bidirectional"))
    )
    (net (code "43") (name "Net-(U$2-CPLL)") (class "Default")
      (node (ref "C34") (pin "1") (pinfunction "1_1") (pintype "passive"))
      (node (ref "U$2") (pin "11") (pinfunction "CPLL_11") (pintype "bidirectional"))
    )
    (net (code "44") (name "Net-(U$2-EGGN)") (class "Default")
      (node (ref "C39") (pin "2") (pinfunction "2_2") (pintype "passive"))
      (node (ref "C43") (pin "1") (pinfunction "1_1") (pintype "passive"))
      (node (ref "R10") (pin "2") (pinfunction "2_2") (pintype "passive"))
      (node (ref "U$2") (pin "7") (pinfunction "EGGN_7") (pintype "bidirectional"))
    )
    (net (code "45") (name "Net-(U$2-EGGP)") (class "Default")
      (node (ref "C39") (pin "1") (pinfunction "1_1") (pintype "passive"))
      (node (ref "C44") (pin "1") (pinfunction "1_1") (pintype "passive"))
      (node (ref "R12") (pin "2") (pinfunction "2_2") (pintype "passive"))
      (node (ref "U$2") (pin "6") (pinfunction "EGGP_6") (pintype "bidirectional"))
    )
    (net (code "46") (name "Net-(U$2-VBG)") (class "Default")
      (node (ref "C52") (pin "1") (pinfunction "1_1") (pintype "passive"))
      (node (ref "U$2") (pin "27") (pinfunction "VBG_27") (pintype "bidirectional"))
    )
    (net (code "47") (name "Net-(U$2-VCM)") (class "Default")
      (node (ref "C51") (pin "1") (pinfunction "1_1") (pintype "passive"))
      (node (ref "U$2") (pin "25") (pinfunction "VCM_25") (pintype "bidirectional"))
    )
    (net (code "48") (name "Net-(U$2-VREF)") (class "Default")
      (node (ref "C45") (pin "1") (pinfunction "1_1") (pintype "passive"))
      (node (ref "U$2") (pin "23") (pinfunction "VREF_23") (pintype "bidirectional"))
    )
    (net (code "49") (name "Net-(U$6-ANT)") (class "Default")
      (node (ref "C15") (pin "1") (pinfunction "1_1") (pintype "passive"))
      (node (ref "L5") (pin "1") (pinfunction "1_1") (pintype "passive"))
      (node (ref "U$6") (pin "P$19") (pinfunction "ANT_P$19") (pintype "bidirectional"))
    )
    (net (code "50") (name "Net-(U$6-DCC)") (class "Default")
      (node (ref "L6") (pin "1") (pinfunction "1_1") (pintype "passive"))
      (node (ref "U$6") (pin "P$31") (pinfunction "DCC_P$31") (pintype "bidirectional"))
    )
    (net (code "51") (name "Net-(U$6-XC1)") (class "Default")
      (node (ref "C14") (pin "1") (pinfunction "1_1") (pintype "passive"))
      (node (ref "U$6") (pin "P$23") (pinfunction "XC1_P$23") (pintype "bidirectional"))
      (node (ref "X3") (pin "1") (pinfunction "1_1") (pintype "passive"))
    )
    (net (code "52") (name "Net-(U$6-XC2)") (class "Default")
      (node (ref "C13") (pin "1") (pinfunction "1_1") (pintype "passive"))
      (node (ref "U$6") (pin "P$24") (pinfunction "XC2_P$24") (pintype "bidirectional"))
      (node (ref "X3") (pin "3") (pinfunction "3_3") (pintype "passive"))
    )
    (net (code "53") (name "P0.12") (class "Default")
      (node (ref "U$6") (pin "P$10") (pinfunction "P0.12_P$10") (pintype "bidirectional"))
    )
    (net (code "54") (name "P0.14") (class "Default")
      (node (ref "U$6") (pin "P$11") (pinfunction "P0.14_P$11") (pintype "bidirectional"))
    )
    (net (code "55") (name "SWDCLK") (class "Default")
      (node (ref "U$6") (pin "P$17") (pinfunction "SWDCLK_P$17") (pintype "bidirectional"))
    )
    (net (code "56") (name "SWDIO") (class "Default")
      (node (ref "R7") (pin "1") (pinfunction "1_1") (pintype "passive"))
      (node (ref "U$1") (pin "5") (pinfunction "5_5") (pintype "bidirectional"))
      (node (ref "U$6") (pin "P$18") (pinfunction "SWDIO_P$18") (pintype "bidirectional"))
    )
    (net (code "57") (name "unconnected-(J6-PadD+)") (class "Default")
      (node (ref "J6") (pin "D+") (pinfunction "D+_D+") (pintype "bidirectional"))
    )
    (net (code "58") (name "unconnected-(J6-PadD-)") (class "Default")
      (node (ref "J6") (pin "D-") (pinfunction "D-_D-") (pintype "bidirectional"))
    )
    (net (code "59") (name "unconnected-(J6-PadID)") (class "Default")
      (node (ref "J6") (pin "ID") (pinfunction "ID_ID") (pintype "bidirectional"))
    )
    (net (code "60") (name "unconnected-(R10-Pad1)") (class "Default")
      (node (ref "R10") (pin "1") (pinfunction "1_1") (pintype "passive"))
    )
    (net (code "61") (name "unconnected-(R12-Pad1)") (class "Default")
      (node (ref "R12") (pin "1") (pinfunction "1_1") (pintype "passive"))
    )
    (net (code "62") (name "unconnected-(S1-Pad2)") (class "Default")
      (node (ref "S1") (pin "2") (pinfunction "2_2") (pintype "bidirectional"))
    )
    (net (code "63") (name "unconnected-(S1-Pad4)") (class "Default")
      (node (ref "S1") (pin "4") (pinfunction "4_4") (pintype "bidirectional"))
    )
    (net (code "64") (name "unconnected-(U$1-Pad3)") (class "Default")
      (node (ref "U$1") (pin "3") (pinfunction "3_3") (pintype "bidirectional"))
    )
    (net (code "65") (name "unconnected-(U$1-Pad10)") (class "Default")
      (node (ref "U$1") (pin "10") (pinfunction "10_10") (pintype "bidirectional"))
    )
  )
)
